# Sheet1.net
KiCad netlist of a schematic drawn in Altium Designer
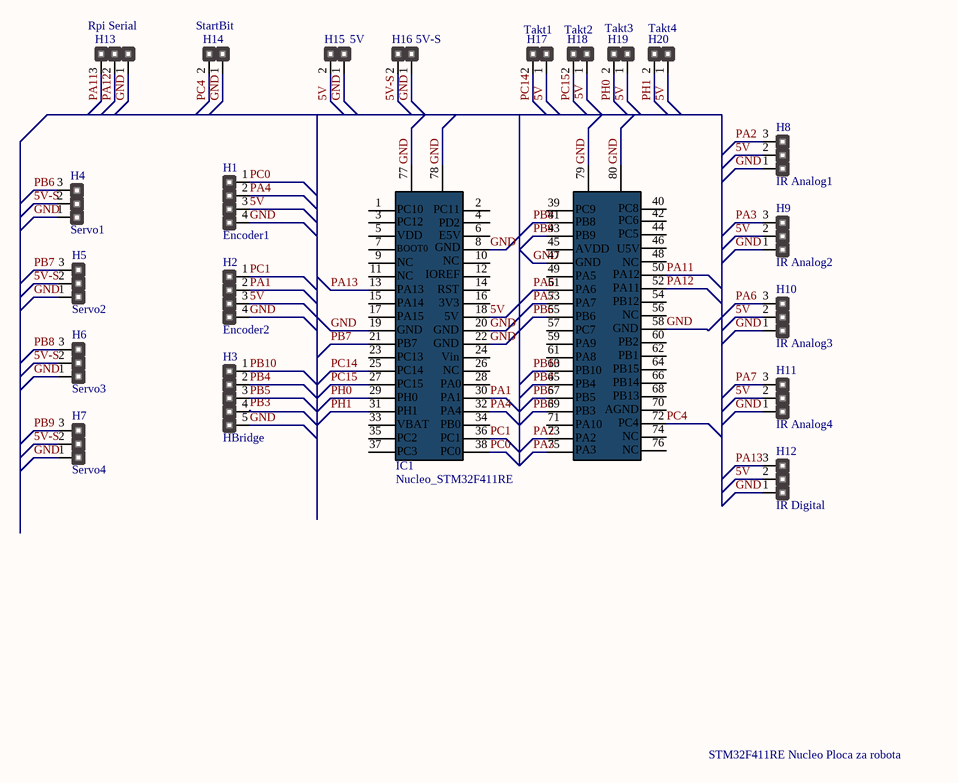
[diagram p0: Sheet1.SchDoc]

(export (version "E")
  (design (tool "Eeschema 10.0.6"))
  (components
    (comp (ref "H1")
      (value "Encoder1")
      (footprint "Header1x4")
      (libsource (lib "KILEX LIB SCH") (part "Header1x4"))
    )
    (comp (ref "H2")
      (value "Encoder2")
      (footprint "Header1x4")
      (libsource (lib "KILEX LIB SCH") (part "Header1x4"))
    )
    (comp (ref "H3")
      (value "HBridge")
      (footprint "Header1x5")
      (libsource (lib "KILEX LIB SCH") (part "Header1x5"))
    )
    (comp (ref "H4")
      (value "Servo1")
      (footprint "Header 1x3")
      (libsource (lib "KILEX LIB SCH") (part "Header 1x3"))
    )
    (comp (ref "H5")
      (value "Servo2")
      (footprint "Header 1x3")
      (libsource (lib "KILEX LIB SCH") (part "Header 1x3"))
    )
    (comp (ref "H6")
      (value "Servo3")
      (footprint "Header 1x3")
      (libsource (lib "KILEX LIB SCH") (part "Header 1x3"))
    )
    (comp (ref "H7")
      (value "Servo4")
      (footprint "Header 1x3")
      (libsource (lib "KILEX LIB SCH") (part "Header 1x3"))
    )
    (comp (ref "H8")
      (value "IR Analog1")
      (footprint "Header 1x3")
      (libsource (lib "KILEX LIB SCH") (part "Header 1x3"))
    )
    (comp (ref "H9")
      (value "IR Analog2")
      (footprint "Header 1x3")
      (libsource (lib "KILEX LIB SCH") (part "Header 1x3"))
    )
    (comp (ref "H10")
      (value "IR Analog3")
      (footprint "Header 1x3")
      (libsource (lib "KILEX LIB SCH") (part "Header 1x3"))
    )
    (comp (ref "H11")
      (value "IR Analog4")
      (footprint "Header 1x3")
      (libsource (lib "KILEX LIB SCH") (part "Header 1x3"))
    )
    (comp (ref "H12")
      (value "IR Digital")
      (footprint "Header 1x3")
      (libsource (lib "KILEX LIB SCH") (part "Header 1x3"))
    )
    (comp (ref "H13")
      (value "Rpi Serial")
      (footprint "Header 1x3")
      (libsource (lib "") (part "Header 1x3_1"))
    )
    (comp (ref "H14")
      (value "StartBit")
      (footprint "Header1x2")
      (libsource (lib "KILEX LIB SCH") (part "Header1x2"))
    )
    (comp (ref "H15")
      (value "5V")
      (footprint "Header1x2")
      (libsource (lib "KILEX LIB SCH") (part "Header1x2"))
    )
    (comp (ref "H16")
      (value "5V-S")
      (footprint "Header1x2")
      (libsource (lib "KILEX LIB SCH") (part "Header1x2"))
    )
    (comp (ref "H17")
      (value "Takt1")
      (footprint "Header1x2")
      (libsource (lib "KILEX LIB SCH") (part "Header1x2"))
    )
    (comp (ref "H18")
      (value "Takt2")
      (footprint "Header1x2")
      (libsource (lib "KILEX LIB SCH") (part "Header1x2"))
    )
    (comp (ref "H19")
      (value "Takt3")
      (footprint "Header1x2")
      (libsource (lib "KILEX LIB SCH") (part "Header1x2"))
    )
    (comp (ref "H20")
      (value "Takt4")
      (footprint "Header1x2")
      (libsource (lib "KILEX LIB SCH") (part "Header1x2"))
    )
    (comp (ref "IC1")
      (value "Nucleo_STM32F411RE")
      (footprint "Nucleo411")
      (libsource (lib "KILEX LIB SCH") (part "Nucleo_STM32F411RE"))
    )
  )
  (nets
    (net (code "1") (name "/5V") (class "Default")
      (node (ref "H1") (pin "3") (pinfunction "3_3") (pintype "passive"))
      (node (ref "H10") (pin "2") (pinfunction "2_2") (pintype "passive"))
      (node (ref "H11") (pin "2") (pinfunction "2_2") (pintype "passive"))
      (node (ref "H12") (pin "2") (pinfunction "2_2") (pintype "passive"))
      (node (ref "H15") (pin "2") (pinfunction "2_2") (pintype "passive"))
      (node (ref "H17") (pin "1") (pinfunction "1_1") (pintype "passive"))
      (node (ref "H18") (pin "1") (pinfunction "1_1") (pintype "passive"))
      (node (ref "H19") (pin "1") (pinfunction "1_1") (pintype "passive"))
      (node (ref "H2") (pin "3") (pinfunction "3_3") (pintype "passive"))
      (node (ref "H20") (pin "1") (pinfunction "1_1") (pintype "passive"))
      (node (ref "H8") (pin "2") (pinfunction "2_2") (pintype "passive"))
      (node (ref "H9") (pin "2") (pinfunction "2_2") (pintype "passive"))
      (node (ref "IC1") (pin "18") (pinfunction "10_18") (pintype "passive"))
    )
    (net (code "2") (name "/5V-S") (class "Default")
      (node (ref "H16") (pin "2") (pinfunction "2_2") (pintype "passive"))
      (node (ref "H4") (pin "2") (pinfunction "2_2") (pintype "passive"))
      (node (ref "H5") (pin "2") (pinfunction "2_2") (pintype "passive"))
      (node (ref "H6") (pin "2") (pinfunction "2_2") (pintype "passive"))
      (node (ref "H7") (pin "2") (pinfunction "2_2") (pintype "passive"))
    )
    (net (code "3") (name "/GND") (class "Default")
      (node (ref "H1") (pin "4") (pinfunction "4_4") (pintype "passive"))
      (node (ref "H10") (pin "1") (pinfunction "1_1") (pintype "passive"))
      (node (ref "H11") (pin "1") (pinfunction "1_1") (pintype "passive"))
      (node (ref "H12") (pin "1") (pinfunction "1_1") (pintype "passive"))
      (node (ref "H13") (pin "1") (pinfunction "1_1") (pintype "passive"))
      (node (ref "H14") (pin "1") (pinfunction "1_1") (pintype "passive"))
      (node (ref "H15") (pin "1") (pinfunction "1_1") (pintype "passive"))
      (node (ref "H16") (pin "1") (pinfunction "1_1") (pintype "passive"))
      (node (ref "H2") (pin "4") (pinfunction "4_4") (pintype "passive"))
      (node (ref "H3") (pin "5") (pinfunction "5_5") (pintype "passive"))
      (node (ref "H4") (pin "1") (pinfunction "1_1") (pintype "passive"))
      (node (ref "H5") (pin "1") (pinfunction "1_1") (pintype "passive"))
      (node (ref "H6") (pin "1") (pinfunction "1_1") (pintype "passive"))
      (node (ref "H7") (pin "1") (pinfunction "1_1") (pintype "passive"))
      (node (ref "H8") (pin "1") (pinfunction "1_1") (pintype "passive"))
      (node (ref "H9") (pin "1") (pinfunction "1_1") (pintype "passive"))
      (node (ref "IC1") (pin "19") (pinfunction "10_19") (pintype "passive"))
      (node (ref "IC1") (pin "20") (pinfunction "11_20") (pintype "passive"))
      (node (ref "IC1") (pin "22") (pinfunction "12_22") (pintype "passive"))
      (node (ref "IC1") (pin "47") (pinfunction "43_47") (pintype "passive"))
      (node (ref "IC1") (pin "58") (pinfunction "49_58") (pintype "passive"))
      (node (ref "IC1") (pin "77") (pinfunction "77_77") (pintype "passive"))
      (node (ref "IC1") (pin "78") (pinfunction "78_78") (pintype "passive"))
      (node (ref "IC1") (pin "79") (pinfunction "79_79") (pintype "passive"))
      (node (ref "IC1") (pin "8") (pinfunction "5_8") (pintype "passive"))
      (node (ref "IC1") (pin "80") (pinfunction "80_80") (pintype "passive"))
    )
    (net (code "4") (name "/PA1") (class "Default")
      (node (ref "H2") (pin "2") (pinfunction "2_2") (pintype "passive"))
      (node (ref "IC1") (pin "30") (pinfunction "16_30") (pintype "passive"))
    )
    (net (code "5") (name "/PA2") (class "Default")
      (node (ref "H8") (pin "3") (pinfunction "3_3") (pintype "passive"))
      (node (ref "IC1") (pin "73") (pinfunction "56_73") (pintype "passive"))
    )
    (net (code "6") (name "/PA3") (class "Default")
      (node (ref "H9") (pin "3") (pinfunction "3_3") (pintype "passive"))
      (node (ref "IC1") (pin "75") (pinfunction "57_75") (pintype "passive"))
    )
    (net (code "7") (name "/PA4") (class "Default")
      (node (ref "H1") (pin "2") (pinfunction "2_2") (pintype "passive"))
      (node (ref "IC1") (pin "32") (pinfunction "17_32") (pintype "passive"))
    )
    (net (code "8") (name "/PA6") (class "Default")
      (node (ref "H10") (pin "3") (pinfunction "3_3") (pintype "passive"))
      (node (ref "IC1") (pin "51") (pinfunction "45_51") (pintype "passive"))
    )
    (net (code "9") (name "/PA7") (class "Default")
      (node (ref "H11") (pin "3") (pinfunction "3_3") (pintype "passive"))
      (node (ref "IC1") (pin "53") (pinfunction "46_53") (pintype "passive"))
    )
    (net (code "10") (name "/PA11") (class "Default")
      (node (ref "H13") (pin "3") (pinfunction "3_3") (pintype "passive"))
      (node (ref "IC1") (pin "50") (pinfunction "45_50") (pintype "passive"))
    )
    (net (code "11") (name "/PA12") (class "Default")
      (node (ref "H13") (pin "2") (pinfunction "2_2") (pintype "passive"))
      (node (ref "IC1") (pin "52") (pinfunction "46_52") (pintype "passive"))
    )
    (net (code "12") (name "/PA13") (class "Default")
      (node (ref "H12") (pin "3") (pinfunction "3_3") (pintype "passive"))
      (node (ref "IC1") (pin "13") (pinfunction "7_13") (pintype "passive"))
    )
    (net (code "13") (name "/PB3") (class "Default")
      (node (ref "H3") (pin "4") (pinfunction "4_4") (pintype "passive"))
      (node (ref "IC1") (pin "69") (pinfunction "54_69") (pintype "passive"))
    )
    (net (code "14") (name "/PB4") (class "Default")
      (node (ref "H3") (pin "2") (pinfunction "2_2") (pintype "passive"))
      (node (ref "IC1") (pin "65") (pinfunction "52_65") (pintype "passive"))
    )
    (net (code "15") (name "/PB5") (class "Default")
      (node (ref "H3") (pin "3") (pinfunction "3_3") (pintype "passive"))
      (node (ref "IC1") (pin "67") (pinfunction "53_67") (pintype "passive"))
    )
    (net (code "16") (name "/PB6") (class "Default")
      (node (ref "H4") (pin "3") (pinfunction "3_3") (pintype "passive"))
      (node (ref "IC1") (pin "55") (pinfunction "47_55") (pintype "passive"))
    )
    (net (code "17") (name "/PB7") (class "Default")
      (node (ref "H5") (pin "3") (pinfunction "3_3") (pintype "passive"))
      (node (ref "IC1") (pin "21") (pinfunction "11_21") (pintype "passive"))
    )
    (net (code "18") (name "/PB8") (class "Default")
      (node (ref "H6") (pin "3") (pinfunction "3_3") (pintype "passive"))
      (node (ref "IC1") (pin "41") (pinfunction "40_41") (pintype "passive"))
    )
    (net (code "19") (name "/PB9") (class "Default")
      (node (ref "H7") (pin "3") (pinfunction "3_3") (pintype "passive"))
      (node (ref "IC1") (pin "43") (pinfunction "41_43") (pintype "passive"))
    )
    (net (code "20") (name "/PB10") (class "Default")
      (node (ref "H3") (pin "1") (pinfunction "1_1") (pintype "passive"))
      (node (ref "IC1") (pin "63") (pinfunction "51_63") (pintype "passive"))
    )
    (net (code "21") (name "/PC0") (class "Default")
      (node (ref "H1") (pin "1") (pinfunction "1_1") (pintype "passive"))
      (node (ref "IC1") (pin "38") (pinfunction "20_38") (pintype "passive"))
    )
    (net (code "22") (name "/PC1") (class "Default")
      (node (ref "H2") (pin "1") (pinfunction "1_1") (pintype "passive"))
      (node (ref "IC1") (pin "36") (pinfunction "19_36") (pintype "passive"))
    )
    (net (code "23") (name "/PC4") (class "Default")
      (node (ref "H14") (pin "2") (pinfunction "2_2") (pintype "passive"))
      (node (ref "IC1") (pin "72") (pinfunction "56_72") (pintype "passive"))
    )
    (net (code "24") (name "/PC14") (class "Default")
      (node (ref "H17") (pin "2") (pinfunction "2_2") (pintype "passive"))
      (node (ref "IC1") (pin "25") (pinfunction "13_25") (pintype "passive"))
    )
    (net (code "25") (name "/PC15") (class "Default")
      (node (ref "H18") (pin "2") (pinfunction "2_2") (pintype "passive"))
      (node (ref "IC1") (pin "27") (pinfunction "14_27") (pintype "passive"))
    )
    (net (code "26") (name "/PH0") (class "Default")
      (node (ref "H19") (pin "2") (pinfunction "2_2") (pintype "passive"))
      (node (ref "IC1") (pin "29") (pinfunction "15_29") (pintype "passive"))
    )
    (net (code "27") (name "/PH1") (class "Default")
      (node (ref "H20") (pin "2") (pinfunction "2_2") (pintype "passive"))
      (node (ref "IC1") (pin "31") (pinfunction "16_31") (pintype "passive"))
    )
    (net (code "28") (name "unconnected-(IC1-2-Pad3)") (class "Default")
      (node (ref "IC1") (pin "3") (pinfunction "2_3") (pintype "passive"))
    )
    (net (code "29") (name "unconnected-(IC1-3-Pad4)") (class "Default")
      (node (ref "IC1") (pin "4") (pinfunction "3_4") (pintype "passive"))
    )
    (net (code "30") (name "unconnected-(IC1-3-Pad5)") (class "Default")
      (node (ref "IC1") (pin "5") (pinfunction "3_5") (pintype "passive"))
    )
    (net (code "31") (name "unconnected-(IC1-4-Pad6)") (class "Default")
      (node (ref "IC1") (pin "6") (pinfunction "4_6") (pintype "passive"))
    )
    (net (code "32") (name "unconnected-(IC1-4-Pad7)") (class "Default")
      (node (ref "IC1") (pin "7") (pinfunction "4_7") (pintype "passive"))
    )
    (net (code "33") (name "unconnected-(IC1-5-Pad9)") (class "Default")
      (node (ref "IC1") (pin "9") (pinfunction "5_9") (pintype "passive"))
    )
    (net (code "34") (name "unconnected-(IC1-6-Pad10)") (class "Default")
      (node (ref "IC1") (pin "10") (pinfunction "6_10") (pintype "passive"))
    )
    (net (code "35") (name "unconnected-(IC1-6-Pad11)") (class "Default")
      (node (ref "IC1") (pin "11") (pinfunction "6_11") (pintype "passive"))
    )
    (net (code "36") (name "unconnected-(IC1-7-Pad12)") (class "Default")
      (node (ref "IC1") (pin "12") (pinfunction "7_12") (pintype "passive"))
    )
    (net (code "37") (name "unconnected-(IC1-8-Pad14)") (class "Default")
      (node (ref "IC1") (pin "14") (pinfunction "8_14") (pintype "passive"))
    )
    (net (code "38") (name "unconnected-(IC1-8-Pad15)") (class "Default")
      (node (ref "IC1") (pin "15") (pinfunction "8_15") (pintype "passive"))
    )
    (net (code "39") (name "unconnected-(IC1-9-Pad16)") (class "Default")
      (node (ref "IC1") (pin "16") (pinfunction "9_16") (pintype "passive"))
    )
    (net (code "40") (name "unconnected-(IC1-9-Pad17)") (class "Default")
      (node (ref "IC1") (pin "17") (pinfunction "9_17") (pintype "passive"))
    )
    (net (code "41") (name "unconnected-(IC1-12-Pad23)") (class "Default")
      (node (ref "IC1") (pin "23") (pinfunction "12_23") (pintype "passive"))
    )
    (net (code "42") (name "unconnected-(IC1-13-Pad24)") (class "Default")
      (node (ref "IC1") (pin "24") (pinfunction "13_24") (pintype "passive"))
    )
    (net (code "43") (name "unconnected-(IC1-14-Pad26)") (class "Default")
      (node (ref "IC1") (pin "26") (pinfunction "14_26") (pintype "passive"))
    )
    (net (code "44") (name "unconnected-(IC1-15-Pad28)") (class "Default")
      (node (ref "IC1") (pin "28") (pinfunction "15_28") (pintype "passive"))
    )
    (net (code "45") (name "unconnected-(IC1-17-Pad33)") (class "Default")
      (node (ref "IC1") (pin "33") (pinfunction "17_33") (pintype "passive"))
    )
    (net (code "46") (name "unconnected-(IC1-18-Pad34)") (class "Default")
      (node (ref "IC1") (pin "34") (pinfunction "18_34") (pintype "passive"))
    )
    (net (code "47") (name "unconnected-(IC1-18-Pad35)") (class "Default")
      (node (ref "IC1") (pin "35") (pinfunction "18_35") (pintype "passive"))
    )
    (net (code "48") (name "unconnected-(IC1-19-Pad37)") (class "Default")
      (node (ref "IC1") (pin "37") (pinfunction "19_37") (pintype "passive"))
    )
    (net (code "49") (name "unconnected-(IC1-41-Pad42)") (class "Default")
      (node (ref "IC1") (pin "42") (pinfunction "41_42") (pintype "passive"))
    )
    (net (code "50") (name "unconnected-(IC1-42-Pad44)") (class "Default")
      (node (ref "IC1") (pin "44") (pinfunction "42_44") (pintype "passive"))
    )
    (net (code "51") (name "unconnected-(IC1-42-Pad45)") (class "Default")
      (node (ref "IC1") (pin "45") (pinfunction "42_45") (pintype "passive"))
    )
    (net (code "52") (name "unconnected-(IC1-43-Pad46)") (class "Default")
      (node (ref "IC1") (pin "46") (pinfunction "43_46") (pintype "passive"))
    )
    (net (code "53") (name "unconnected-(IC1-44-Pad48)") (class "Default")
      (node (ref "IC1") (pin "48") (pinfunction "44_48") (pintype "passive"))
    )
    (net (code "54") (name "unconnected-(IC1-44-Pad49)") (class "Default")
      (node (ref "IC1") (pin "49") (pinfunction "44_49") (pintype "passive"))
    )
    (net (code "55") (name "unconnected-(IC1-47-Pad54)") (class "Default")
      (node (ref "IC1") (pin "54") (pinfunction "47_54") (pintype "passive"))
    )
    (net (code "56") (name "unconnected-(IC1-48-Pad56)") (class "Default")
      (node (ref "IC1") (pin "56") (pinfunction "48_56") (pintype "passive"))
    )
    (net (code "57") (name "unconnected-(IC1-48-Pad57)") (class "Default")
      (node (ref "IC1") (pin "57") (pinfunction "48_57") (pintype "passive"))
    )
    (net (code "58") (name "unconnected-(IC1-49-Pad59)") (class "Default")
      (node (ref "IC1") (pin "59") (pinfunction "49_59") (pintype "passive"))
    )
    (net (code "59") (name "unconnected-(IC1-50-Pad60)") (class "Default")
      (node (ref "IC1") (pin "60") (pinfunction "50_60") (pintype "passive"))
    )
    (net (code "60") (name "unconnected-(IC1-50-Pad61)") (class "Default")
      (node (ref "IC1") (pin "61") (pinfunction "50_61") (pintype "passive"))
    )
    (net (code "61") (name "unconnected-(IC1-51-Pad62)") (class "Default")
      (node (ref "IC1") (pin "62") (pinfunction "51_62") (pintype "passive"))
    )
    (net (code "62") (name "unconnected-(IC1-52-Pad64)") (class "Default")
      (node (ref "IC1") (pin "64") (pinfunction "52_64") (pintype "passive"))
    )
    (net (code "63") (name "unconnected-(IC1-53-Pad66)") (class "Default")
      (node (ref "IC1") (pin "66") (pinfunction "53_66") (pintype "passive"))
    )
    (net (code "64") (name "unconnected-(IC1-54-Pad68)") (class "Default")
      (node (ref "IC1") (pin "68") (pinfunction "54_68") (pintype "passive"))
    )
    (net (code "65") (name "unconnected-(IC1-55-Pad70)") (class "Default")
      (node (ref "IC1") (pin "70") (pinfunction "55_70") (pintype "passive"))
    )
    (net (code "66") (name "unconnected-(IC1-55-Pad71)") (class "Default")
      (node (ref "IC1") (pin "71") (pinfunction "55_71") (pintype "passive"))
    )
    (net (code "67") (name "unconnected-(IC1-57-Pad74)") (class "Default")
      (node (ref "IC1") (pin "74") (pinfunction "57_74") (pintype "passive"))
    )
    (net (code "68") (name "unconnected-(IC1-58-Pad76)") (class "Default")
      (node (ref "IC1") (pin "76") (pinfunction "58_76") (pintype "passive"))
    )
    (net (code "69") (name "unconnected-(IC1-Pad1)") (class "Default")
      (node (ref "IC1") (pin "1") (pinfunction "1_1") (pintype "passive"))
    )
    (net (code "70") (name "unconnected-(IC1-Pad2)") (class "Default")
      (node (ref "IC1") (pin "2") (pinfunction "2_2") (pintype "passive"))
    )
    (net (code "71") (name "unconnected-(IC1-Pad39)") (class "Default")
      (node (ref "IC1") (pin "39") (pinfunction "39_39") (pintype "passive"))
    )
    (net (code "72") (name "unconnected-(IC1-Pad40)") (class "Default")
      (node (ref "IC1") (pin "40") (pinfunction "40_40") (pintype "passive"))
    )
  )
)
